# Status.net
KiCad netlist of a schematic drawn in Altium Designer
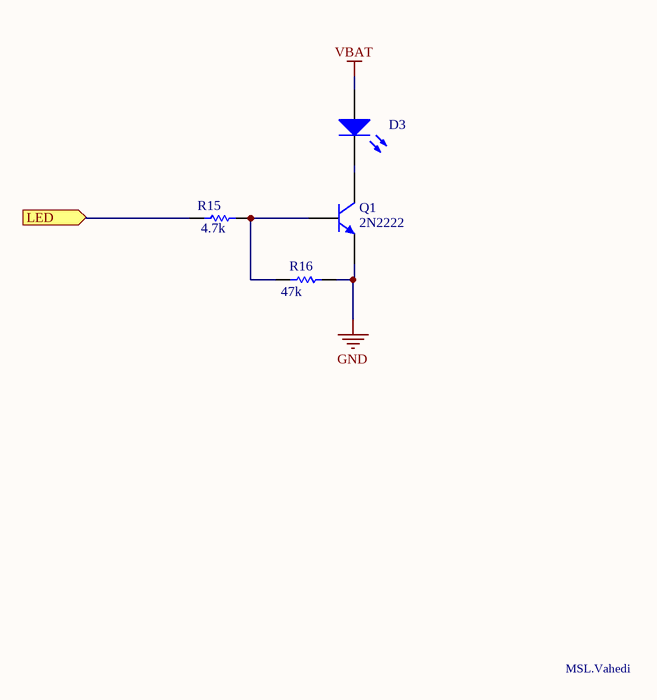
[diagram p0: Status.SchDoc]

(export (version "E")
  (design (tool "Eeschema 10.0.6"))
  (components
    (comp (ref "D3")
      (value "~")
      (footprint "LED_0805_BLUE")
      (description "Typical INFRARED GaAs LED")
      (fields (field (name "PUBLISHER") "Altium Limited"))
      (libsource (lib "Miscellaneous Devices") (part "LED0"))
    )
    (comp (ref "Q1")
      (value "2N2222")
      (footprint "SOT-23")
      (description "NPN General Purpose Amplifier")
      (fields (field (name "PUBLISHER") "Altium Limited"))
      (libsource (lib "Miscellaneous Devices") (part "2N3904"))
    )
    (comp (ref "R15")
      (value "4.7k")
      (footprint "RES0805")
      (description "Resistor")
      (fields (field (name "PUBLISHER") "Altium Limited"))
      (libsource (lib "Miscellaneous Devices") (part "Res1"))
    )
    (comp (ref "R16")
      (value "47k")
      (footprint "RES0805")
      (description "Resistor")
      (fields (field (name "PUBLISHER") "Altium Limited"))
      (libsource (lib "Miscellaneous Devices") (part "Res1"))
    )
  )
  (nets
    (net (code "1") (name "/LED") (class "Default")
      (node (ref "R15") (pin "1") (pinfunction "1_1") (pintype "passive"))
    )
    (net (code "2") (name "GND") (class "Default")
      (node (ref "Q1") (pin "1") (pinfunction "E_1") (pintype "passive"))
      (node (ref "R16") (pin "2") (pinfunction "2_2") (pintype "passive"))
    )
    (net (code "3") (name "Net-(D3-K)") (class "Default")
      (node (ref "D3") (pin "2") (pinfunction "K_2") (pintype "passive"))
      (node (ref "Q1") (pin "3") (pinfunction "C_3") (pintype "passive"))
    )
    (net (code "4") (name "Net-(Q1-B)") (class "Default")
      (node (ref "Q1") (pin "2") (pinfunction "B_2") (pintype "passive"))
      (node (ref "R15") (pin "2") (pinfunction "2_2") (pintype "passive"))
      (node (ref "R16") (pin "1") (pinfunction "1_1") (pintype "passive"))
    )
    (net (code "5") (name "VBAT") (class "Default")
      (node (ref "D3") (pin "1") (pinfunction "A_1") (pintype "passive"))
    )
  )
)
